# Tx_power.net
KiCad netlist of a schematic drawn in Altium Designer
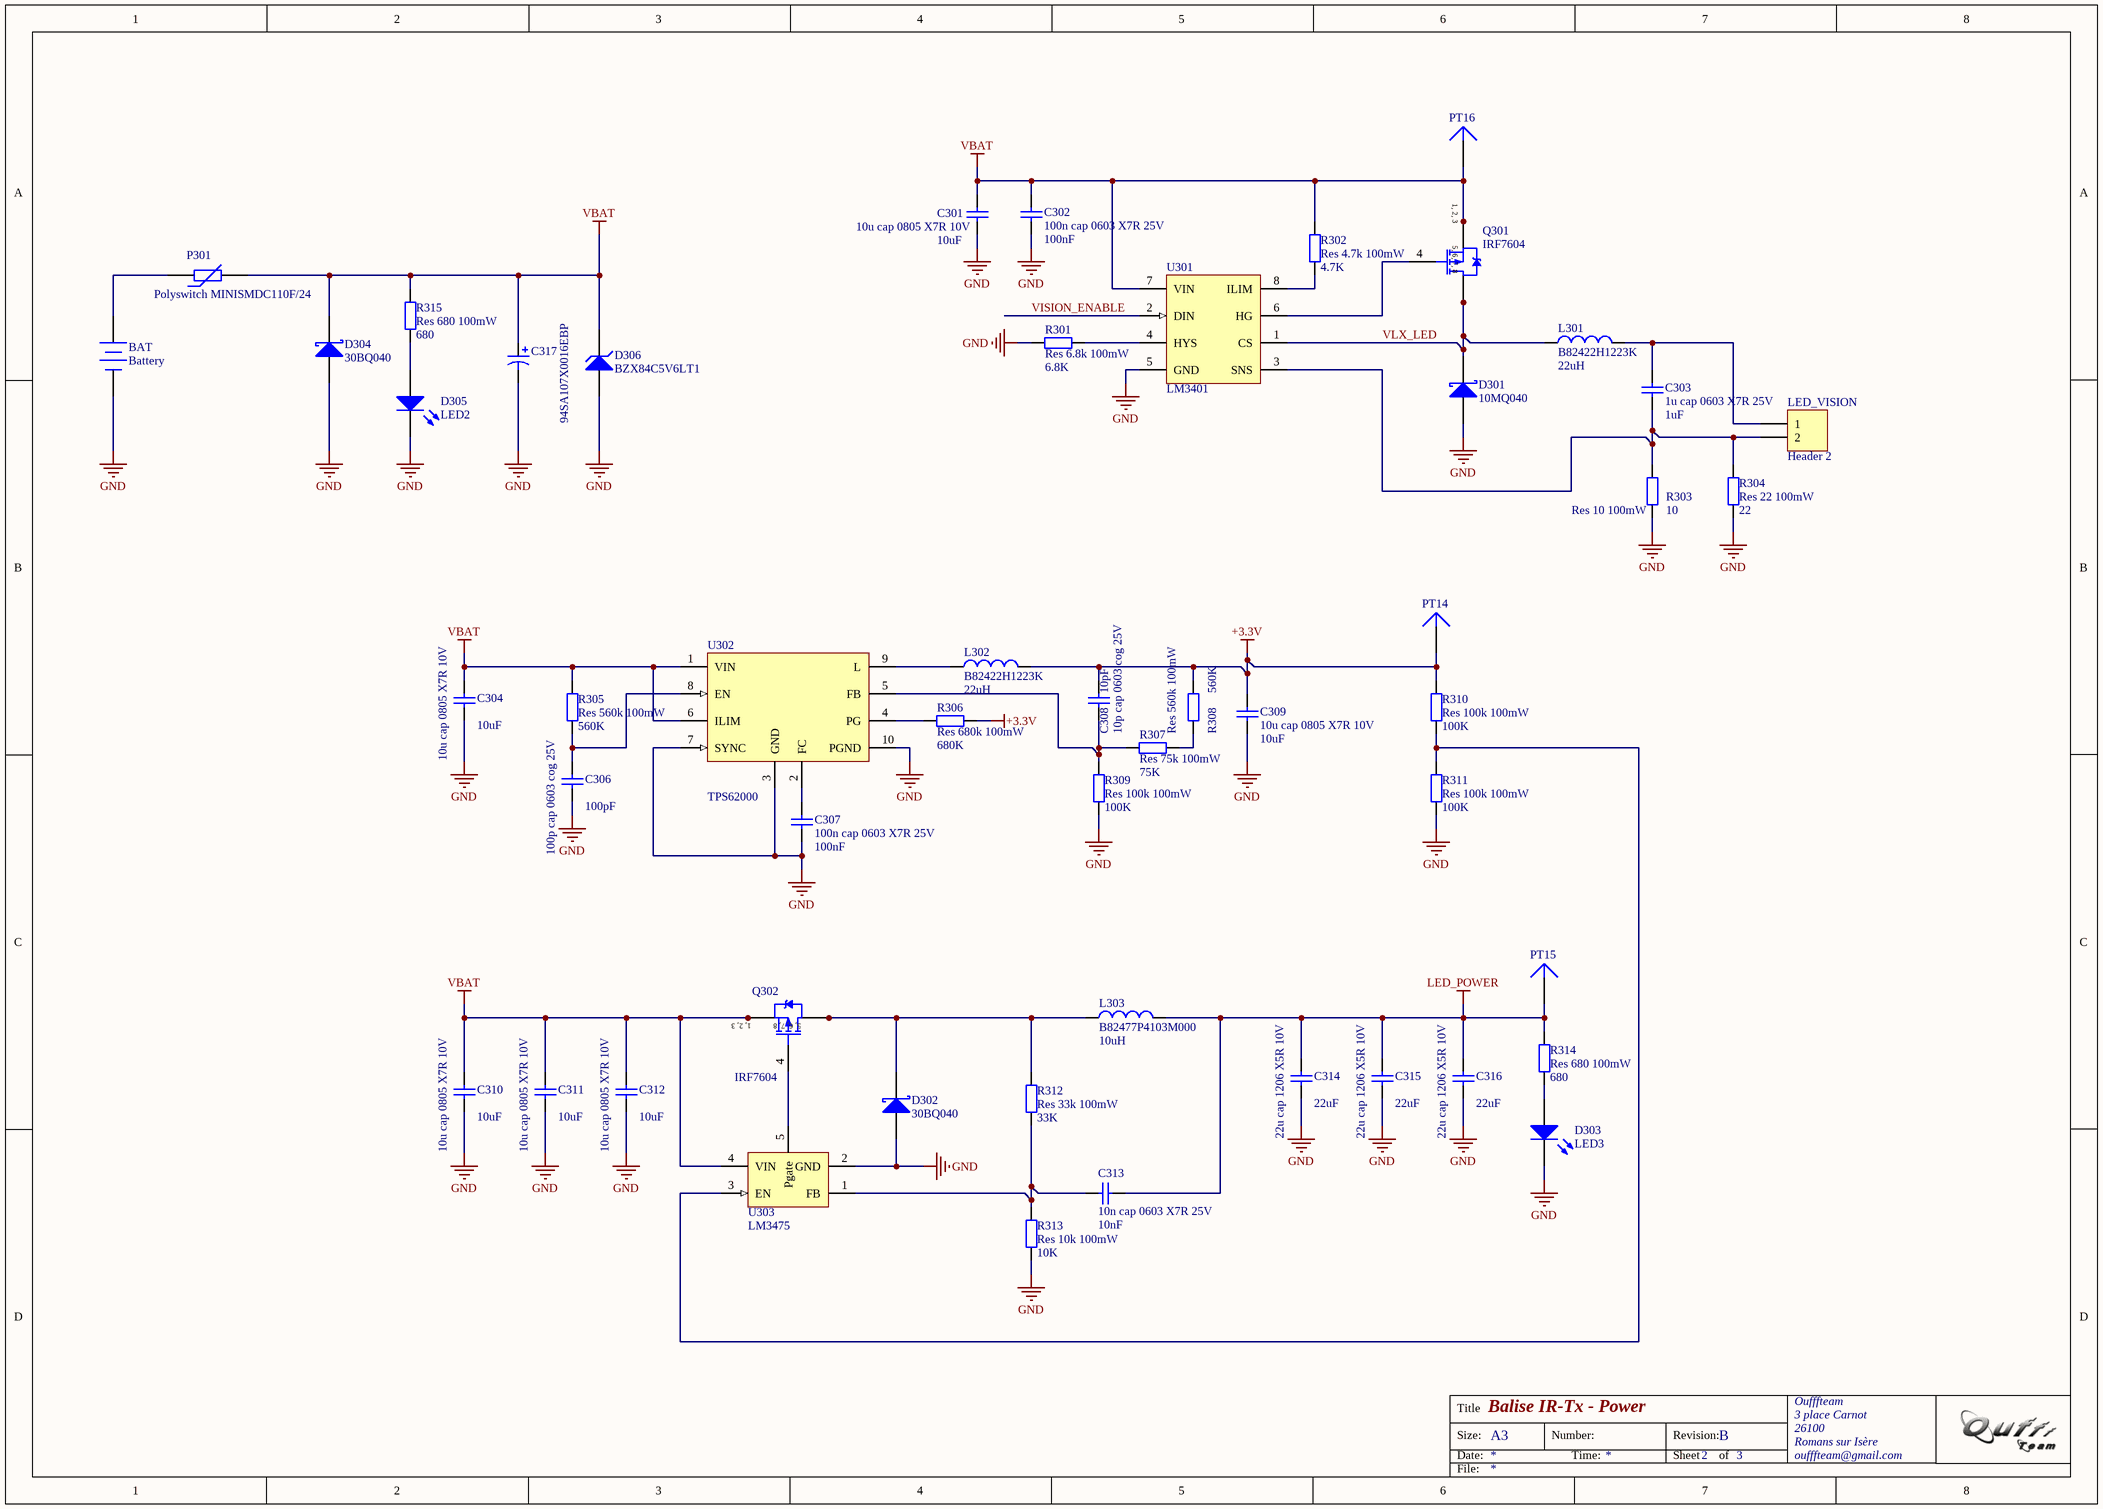
[diagram p0: Tx_power.SchDoc]

(export (version "E")
  (design (tool "Eeschema 10.0.6"))
  (components
    (comp (ref "BAT")
      (value "Battery")
      (footprint "BAT-2")
      (description "Multicell Battery")
      (fields (field (name "PUBLISHER") "Altium Limited"))
      (libsource (lib "Miscellaneous Devices") (part "Battery"))
    )
    (comp (ref "C301")
      (value "10u cap 0805 X7R 10V")
      (footprint "0805")
      (description "Capacitor")
      (fields (field (name "ALTIUM_VALUE") "10uF") (field (name "PUBLISHER") "Altium Limited"))
      (libsource (lib "Miscellaneous Devices") (part "Cap"))
    )
    (comp (ref "C302")
      (value "100n cap 0603 X7R 25V")
      (footprint "0603")
      (description "Capacitor")
      (fields (field (name "ALTIUM_VALUE") "100nF") (field (name "PUBLISHER") "Altium Limited"))
      (libsource (lib "Miscellaneous Devices") (part "Cap"))
    )
    (comp (ref "C303")
      (value "1u cap 0603 X7R 25V")
      (footprint "0603")
      (description "Capacitor")
      (fields (field (name "ALTIUM_VALUE") "1uF") (field (name "PUBLISHER") "Altium Limited"))
      (libsource (lib "Miscellaneous Devices") (part "Cap"))
    )
    (comp (ref "C304")
      (value "10u cap 0805 X7R 10V")
      (footprint "0805")
      (description "Capacitor")
      (fields (field (name "ALTIUM_VALUE") "10uF") (field (name "PUBLISHER") "Altium Limited"))
      (libsource (lib "Miscellaneous Devices") (part "Cap"))
    )
    (comp (ref "C306")
      (value "100p cap 0603 cog 25V")
      (footprint "0603")
      (description "Capacitor")
      (fields (field (name "ALTIUM_VALUE") "100pF") (field (name "PUBLISHER") "Altium Limited"))
      (libsource (lib "Miscellaneous Devices") (part "Cap"))
    )
    (comp (ref "C307")
      (value "100n cap 0603 X7R 25V")
      (footprint "0603")
      (description "Capacitor")
      (fields (field (name "ALTIUM_VALUE") "100nF") (field (name "PUBLISHER") "Altium Limited"))
      (libsource (lib "Miscellaneous Devices") (part "Cap"))
    )
    (comp (ref "C308")
      (value "10p cap 0603 cog 25V")
      (footprint "0603")
      (description "Capacitor")
      (fields (field (name "ALTIUM_VALUE") "10pF") (field (name "PUBLISHER") "Altium Limited"))
      (libsource (lib "Miscellaneous Devices") (part "Cap"))
    )
    (comp (ref "C309")
      (value "10u cap 0805 X7R 10V")
      (footprint "0805")
      (description "Capacitor")
      (fields (field (name "ALTIUM_VALUE") "10uF") (field (name "PUBLISHER") "Altium Limited"))
      (libsource (lib "Miscellaneous Devices") (part "Cap"))
    )
    (comp (ref "C310")
      (value "10u cap 0805 X7R 10V")
      (footprint "0805")
      (description "Capacitor")
      (fields (field (name "ALTIUM_VALUE") "10uF") (field (name "PUBLISHER") "Altium Limited"))
      (libsource (lib "Miscellaneous Devices") (part "Cap"))
    )
    (comp (ref "C311")
      (value "10u cap 0805 X7R 10V")
      (footprint "0805")
      (description "Capacitor")
      (fields (field (name "ALTIUM_VALUE") "10uF") (field (name "PUBLISHER") "Altium Limited"))
      (libsource (lib "Miscellaneous Devices") (part "Cap"))
    )
    (comp (ref "C312")
      (value "10u cap 0805 X7R 10V")
      (footprint "0805")
      (description "Capacitor")
      (fields (field (name "ALTIUM_VALUE") "10uF") (field (name "PUBLISHER") "Altium Limited"))
      (libsource (lib "Miscellaneous Devices") (part "Cap"))
    )
    (comp (ref "C313")
      (value "10n cap 0603 X7R 25V")
      (footprint "0603")
      (description "Capacitor")
      (fields (field (name "ALTIUM_VALUE") "10nF") (field (name "PUBLISHER") "Altium Limited"))
      (libsource (lib "Miscellaneous Devices") (part "Cap"))
    )
    (comp (ref "C314")
      (value "22u cap 1206 X5R 10V")
      (footprint "1206")
      (description "Capacitor")
      (fields (field (name "ALTIUM_VALUE") "22uF") (field (name "PUBLISHER") "Altium Limited"))
      (libsource (lib "Miscellaneous Devices") (part "Cap"))
    )
    (comp (ref "C315")
      (value "22u cap 1206 X5R 10V")
      (footprint "1206")
      (description "Capacitor")
      (fields (field (name "ALTIUM_VALUE") "22uF") (field (name "PUBLISHER") "Altium Limited"))
      (libsource (lib "Miscellaneous Devices") (part "Cap"))
    )
    (comp (ref "C316")
      (value "22u cap 1206 X5R 10V")
      (footprint "1206")
      (description "Capacitor")
      (fields (field (name "ALTIUM_VALUE") "22uF") (field (name "PUBLISHER") "Altium Limited"))
      (libsource (lib "Miscellaneous Devices") (part "Cap"))
    )
    (comp (ref "C317")
      (value "94SA107X0016EBP")
      (footprint "E")
      (description "Solid Aluminum Capacitor with Organic Semiconductor Electrolyte: 100uF, 16V, Bulk Pack")
      (fields (field (name "PUBLISHER") "Altium Limited"))
      (libsource (lib "Vishay Electrolytic Radial-Lead Capacitor") (part "94SA107X0016EBP"))
    )
    (comp (ref "D301")
      (value "10MQ040")
      (footprint "D-64")
      (description "Schottky Rectifier")
      (fields (field (name "PUBLISHER") "Altium Limited"))
      (libsource (lib "IR Rectifier - Schottky") (part "10MQ040"))
    )
    (comp (ref "D302")
      (value "30BQ040")
      (footprint "SMC")
      (description "Schottky Rectifier")
      (fields (field (name "PUBLISHER") "Altium Limited"))
      (libsource (lib "IR Rectifier - Schottky") (part "30BQ040"))
    )
    (comp (ref "D303")
      (value "LED3")
      (footprint "0603")
      (description "Typical BLUE SiC LED")
      (fields (field (name "PUBLISHER") "Altium Limited"))
      (libsource (lib "Miscellaneous Devices") (part "LED3"))
    )
    (comp (ref "D304")
      (value "30BQ040")
      (footprint "SMC")
      (description "Schottky Rectifier")
      (fields (field (name "PUBLISHER") "Altium Limited"))
      (libsource (lib "IR Rectifier - Schottky") (part "30BQ040"))
    )
    (comp (ref "D305")
      (value "LED2")
      (footprint "0603")
      (description "Typical RED, GREEN, YELLOW, AMBER GaAs LED")
      (fields (field (name "PUBLISHER") "Altium Limited"))
      (libsource (lib "Miscellaneous Devices") (part "LED2"))
    )
    (comp (ref "D306")
      (value "BZX84C5V6LT1")
      (footprint "318-07")
      (description "Zener Voltage Regulator Diode")
      (fields (field (name "PUBLISHER") "Altium Limited"))
      (libsource (lib "Motorola Discrete Diode") (part "BZX84C5V6LT1"))
    )
    (comp (ref "L301")
      (value "B82422H1223K")
      (footprint "1210")
      (description "Inductor")
      (fields (field (name "ALTIUM_VALUE") "22uH") (field (name "PUBLISHER") "Altium Limited"))
      (libsource (lib "Miscellaneous Devices") (part "Inductor"))
    )
    (comp (ref "L302")
      (value "B82422H1223K")
      (footprint "1210")
      (description "Inductor")
      (fields (field (name "ALTIUM_VALUE") "22uH") (field (name "PUBLISHER") "Altium Limited"))
      (libsource (lib "Miscellaneous Devices") (part "Inductor"))
    )
    (comp (ref "L303")
      (value "B82477P4103M000")
      (footprint "B82477P4103M000")
      (description "Inductor")
      (fields (field (name "ALTIUM_VALUE") "10uH") (field (name "PUBLISHER") "Altium Limited"))
      (libsource (lib "Miscellaneous Devices") (part "Inductor"))
    )
    (comp (ref "LED_VISION")
      (value "Header 2")
      (footprint "HDR1X2")
      (description "Header, 2-Pin")
      (fields (field (name "PUBLISHER") "Altium Limited"))
      (libsource (lib "Miscellaneous Connectors") (part "Header 2"))
    )
    (comp (ref "P301")
      (value "Polyswitch MINISMDC110F/24")
      (footprint "1812")
      (description "Varistor (Voltage-Sensitive Resistor)")
      (fields (field (name "PUBLISHER") "Altium Limited"))
      (libsource (lib "Miscellaneous Devices") (part "Res Varistor"))
    )
    (comp (ref "PT14")
      (value "Plug")
      (footprint "TP")
      (fields (field (name "PUBLISHER") "Altium Limited"))
      (libsource (lib "Miscellaneous Connectors") (part "Plug"))
    )
    (comp (ref "PT15")
      (value "Plug")
      (footprint "TP")
      (fields (field (name "PUBLISHER") "Altium Limited"))
      (libsource (lib "Miscellaneous Connectors") (part "Plug"))
    )
    (comp (ref "PT16")
      (value "Plug")
      (footprint "TP")
      (fields (field (name "PUBLISHER") "Altium Limited"))
      (libsource (lib "Miscellaneous Connectors") (part "Plug"))
    )
    (comp (ref "Q301")
      (value "IRF7604")
      (footprint "Micro8")
      (description "HEXFET Power MOSFET")
      (fields (field (name "PUBLISHER") "Altium Limited"))
      (libsource (lib "IR Discrete MOSFET - Power") (part "IRF7604"))
    )
    (comp (ref "Q302")
      (value "IRF7604")
      (footprint "Micro8")
      (description "HEXFET Power MOSFET")
      (fields (field (name "PUBLISHER") "Altium Limited"))
      (libsource (lib "IR Discrete MOSFET - Power") (part "IRF7604"))
    )
    (comp (ref "R301")
      (value "Res 6.8k 100mW")
      (footprint "0603")
      (description "Resistor")
      (fields (field (name "ALTIUM_VALUE") "6.8K") (field (name "PUBLISHER") "Altium Limited"))
      (libsource (lib "") (part "Res2_1"))
    )
    (comp (ref "R302")
      (value "Res 4.7k 100mW")
      (footprint "0603")
      (description "Resistor")
      (fields (field (name "ALTIUM_VALUE") "4.7K") (field (name "PUBLISHER") "Altium Limited"))
      (libsource (lib "Miscellaneous Devices") (part "Res2"))
    )
    (comp (ref "R303")
      (value "Res 10 100mW")
      (footprint "0603")
      (description "Resistor")
      (fields (field (name "ALTIUM_VALUE") "10") (field (name "PUBLISHER") "Altium Limited"))
      (libsource (lib "Miscellaneous Devices") (part "Res2"))
    )
    (comp (ref "R304")
      (value "Res 22 100mW")
      (footprint "0603")
      (description "Resistor")
      (fields (field (name "ALTIUM_VALUE") "22") (field (name "PUBLISHER") "Altium Limited"))
      (libsource (lib "Miscellaneous Devices") (part "Res2"))
    )
    (comp (ref "R305")
      (value "Res 560k 100mW")
      (footprint "0603")
      (description "Resistor")
      (fields (field (name "ALTIUM_VALUE") "560K") (field (name "PUBLISHER") "Altium Limited"))
      (libsource (lib "Miscellaneous Devices") (part "Res2"))
    )
    (comp (ref "R306")
      (value "Res 680k 100mW")
      (footprint "0603")
      (description "Resistor")
      (fields (field (name "ALTIUM_VALUE") "680K") (field (name "PUBLISHER") "Altium Limited"))
      (libsource (lib "") (part "Res2_1"))
    )
    (comp (ref "R307")
      (value "Res 75k 100mW")
      (footprint "0603")
      (description "Resistor")
      (fields (field (name "ALTIUM_VALUE") "75K") (field (name "PUBLISHER") "Altium Limited"))
      (libsource (lib "") (part "Res2_1"))
    )
    (comp (ref "R308")
      (value "Res 560k 100mW")
      (footprint "0603")
      (description "Resistor")
      (fields (field (name "ALTIUM_VALUE") "560K") (field (name "PUBLISHER") "Altium Limited"))
      (libsource (lib "Miscellaneous Devices") (part "Res2"))
    )
    (comp (ref "R309")
      (value "Res 100k 100mW")
      (footprint "0603")
      (description "Resistor")
      (fields (field (name "ALTIUM_VALUE") "100K") (field (name "PUBLISHER") "Altium Limited"))
      (libsource (lib "Miscellaneous Devices") (part "Res2"))
    )
    (comp (ref "R310")
      (value "Res 100k 100mW")
      (footprint "0603")
      (description "Resistor")
      (fields (field (name "ALTIUM_VALUE") "100K") (field (name "PUBLISHER") "Altium Limited"))
      (libsource (lib "Miscellaneous Devices") (part "Res2"))
    )
    (comp (ref "R311")
      (value "Res 100k 100mW")
      (footprint "0603")
      (description "Resistor")
      (fields (field (name "ALTIUM_VALUE") "100K") (field (name "PUBLISHER") "Altium Limited"))
      (libsource (lib "Miscellaneous Devices") (part "Res2"))
    )
    (comp (ref "R312")
      (value "Res 33k 100mW")
      (footprint "0603")
      (description "Resistor")
      (fields (field (name "ALTIUM_VALUE") "33K") (field (name "PUBLISHER") "Altium Limited"))
      (libsource (lib "Miscellaneous Devices") (part "Res2"))
    )
    (comp (ref "R313")
      (value "Res 10k 100mW")
      (footprint "0603")
      (description "Resistor")
      (fields (field (name "ALTIUM_VALUE") "10K") (field (name "PUBLISHER") "Altium Limited"))
      (libsource (lib "Miscellaneous Devices") (part "Res2"))
    )
    (comp (ref "R314")
      (value "Res 680 100mW")
      (footprint "0603")
      (description "Resistor")
      (fields (field (name "ALTIUM_VALUE") "680") (field (name "PUBLISHER") "Altium Limited"))
      (libsource (lib "Miscellaneous Devices") (part "Res2"))
    )
    (comp (ref "R315")
      (value "Res 680 100mW")
      (footprint "0603")
      (description "Resistor")
      (fields (field (name "ALTIUM_VALUE") "680") (field (name "PUBLISHER") "Altium Limited"))
      (libsource (lib "Miscellaneous Devices") (part "Res2"))
    )
    (comp (ref "U301")
      (value "LM3401")
      (footprint "MSOP8")
      (description "Hysteretic PFET Controller for High Power LED Drive")
      (libsource (lib "Oufff_Lib2") (part "LM3401"))
    )
    (comp (ref "U302")
      (value "TPS62000")
      (footprint "MS10")
      (description "HIGH-EFFICIENCY STEP-DOWN LOW POWER DC-DC CONVERTER")
      (libsource (lib "Oufff_Lib2") (part "TPS6200x"))
    )
    (comp (ref "U303")
      (value "LM3475")
      (footprint "SOT23-5")
      (description "Hysteretic PFET Buck Controller")
      (libsource (lib "Oufff_Lib2") (part "LM3475"))
    )
  )
  (nets
    (net (code "1") (name "+3.3V") (class "Default")
      (node (ref "C308") (pin "2") (pinfunction "2_2") (pintype "passive"))
      (node (ref "C309") (pin "2") (pinfunction "2_2") (pintype "passive"))
      (node (ref "L302") (pin "2") (pinfunction "2_2") (pintype "passive"))
      (node (ref "PT14") (pin "1") (pinfunction "1_1") (pintype "passive"))
      (node (ref "R306") (pin "2") (pinfunction "2_2") (pintype "passive"))
      (node (ref "R308") (pin "2") (pinfunction "2_2") (pintype "passive"))
      (node (ref "R310") (pin "2") (pinfunction "2_2") (pintype "passive"))
    )
    (net (code "2") (name "/VISION_ENABLE") (class "Default")
      (node (ref "U301") (pin "2") (pinfunction "DIN_2") (pintype "input"))
    )
    (net (code "3") (name "/VLX_LED") (class "Default")
      (node (ref "D301") (pin "2") (pinfunction "K_2") (pintype "passive"))
      (node (ref "L301") (pin "1") (pinfunction "1_1") (pintype "passive"))
      (node (ref "Q301") (pin "5") (pinfunction "D_5") (pintype "passive"))
      (node (ref "Q301") (pin "6") (pinfunction "D_6") (pintype "passive"))
      (node (ref "Q301") (pin "7") (pinfunction "D_7") (pintype "passive"))
      (node (ref "Q301") (pin "8") (pinfunction "D_8") (pintype "passive"))
      (node (ref "U301") (pin "1") (pinfunction "CS_1") (pintype "passive"))
    )
    (net (code "4") (name "GND") (class "Default")
      (node (ref "BAT") (pin "2") (pinfunction "-_2") (pintype "passive"))
      (node (ref "C301") (pin "1") (pinfunction "1_1") (pintype "passive"))
      (node (ref "C302") (pin "1") (pinfunction "1_1") (pintype "passive"))
      (node (ref "C304") (pin "1") (pinfunction "1_1") (pintype "passive"))
      (node (ref "C306") (pin "1") (pinfunction "1_1") (pintype "passive"))
      (node (ref "C307") (pin "1") (pinfunction "1_1") (pintype "passive"))
      (node (ref "C309") (pin "1") (pinfunction "1_1") (pintype "passive"))
      (node (ref "C310") (pin "1") (pinfunction "1_1") (pintype "passive"))
      (node (ref "C311") (pin "1") (pinfunction "1_1") (pintype "passive"))
      (node (ref "C312") (pin "1") (pinfunction "1_1") (pintype "passive"))
      (node (ref "C314") (pin "1") (pinfunction "1_1") (pintype "passive"))
      (node (ref "C315") (pin "1") (pinfunction "1_1") (pintype "passive"))
      (node (ref "C316") (pin "1") (pinfunction "1_1") (pintype "passive"))
      (node (ref "C317") (pin "2") (pinfunction "2_2") (pintype "passive"))
      (node (ref "D301") (pin "1") (pinfunction "A_1") (pintype "passive"))
      (node (ref "D302") (pin "1") (pinfunction "A_1") (pintype "passive"))
      (node (ref "D303") (pin "2") (pinfunction "K_2") (pintype "passive"))
      (node (ref "D304") (pin "1") (pinfunction "A_1") (pintype "passive"))
      (node (ref "D305") (pin "2") (pinfunction "K_2") (pintype "passive"))
      (node (ref "D306") (pin "1") (pinfunction "A_1") (pintype "passive"))
      (node (ref "R301") (pin "1") (pinfunction "1_1") (pintype "passive"))
      (node (ref "R303") (pin "1") (pinfunction "1_1") (pintype "passive"))
      (node (ref "R304") (pin "1") (pinfunction "1_1") (pintype "passive"))
      (node (ref "R309") (pin "1") (pinfunction "1_1") (pintype "passive"))
      (node (ref "R311") (pin "1") (pinfunction "1_1") (pintype "passive"))
      (node (ref "R313") (pin "1") (pinfunction "1_1") (pintype "passive"))
      (node (ref "U301") (pin "5") (pinfunction "GND_5") (pintype "power_in"))
      (node (ref "U302") (pin "10") (pinfunction "PGND_10") (pintype "power_in"))
      (node (ref "U302") (pin "3") (pinfunction "GND_3") (pintype "power_in"))
      (node (ref "U302") (pin "7") (pinfunction "SYNC_7") (pintype "input"))
      (node (ref "U303") (pin "2") (pinfunction "GND_2") (pintype "power_in"))
    )
    (net (code "5") (name "LED_POWER") (class "Default")
      (node (ref "C313") (pin "2") (pinfunction "2_2") (pintype "passive"))
      (node (ref "C314") (pin "2") (pinfunction "2_2") (pintype "passive"))
      (node (ref "C315") (pin "2") (pinfunction "2_2") (pintype "passive"))
      (node (ref "C316") (pin "2") (pinfunction "2_2") (pintype "passive"))
      (node (ref "L303") (pin "2") (pinfunction "2_2") (pintype "passive"))
      (node (ref "PT15") (pin "1") (pinfunction "1_1") (pintype "passive"))
      (node (ref "R314") (pin "2") (pinfunction "2_2") (pintype "passive"))
    )
    (net (code "6") (name "Net-(BAT-+)") (class "Default")
      (node (ref "BAT") (pin "1") (pinfunction "+_1") (pintype "passive"))
      (node (ref "P301") (pin "1") (pinfunction "1_1") (pintype "passive"))
    )
    (net (code "7") (name "Net-(C303-Pad2)") (class "Default")
      (node (ref "C303") (pin "2") (pinfunction "2_2") (pintype "passive"))
      (node (ref "L301") (pin "2") (pinfunction "2_2") (pintype "passive"))
      (node (ref "LED_VISION") (pin "1") (pinfunction "1_1") (pintype "passive"))
    )
    (net (code "8") (name "Net-(D302-K)") (class "Default")
      (node (ref "D302") (pin "2") (pinfunction "K_2") (pintype "passive"))
      (node (ref "L303") (pin "1") (pinfunction "1_1") (pintype "passive"))
      (node (ref "Q302") (pin "5") (pinfunction "D_5") (pintype "passive"))
      (node (ref "Q302") (pin "6") (pinfunction "D_6") (pintype "passive"))
      (node (ref "Q302") (pin "7") (pinfunction "D_7") (pintype "passive"))
      (node (ref "Q302") (pin "8") (pinfunction "D_8") (pintype "passive"))
      (node (ref "R312") (pin "2") (pinfunction "2_2") (pintype "passive"))
    )
    (net (code "9") (name "Net-(D303-A)") (class "Default")
      (node (ref "D303") (pin "1") (pinfunction "A_1") (pintype "passive"))
      (node (ref "R314") (pin "1") (pinfunction "1_1") (pintype "passive"))
    )
    (net (code "10") (name "Net-(D305-A)") (class "Default")
      (node (ref "D305") (pin "1") (pinfunction "A_1") (pintype "passive"))
      (node (ref "R315") (pin "1") (pinfunction "1_1") (pintype "passive"))
    )
    (net (code "11") (name "Net-(Q301-G)") (class "Default")
      (node (ref "Q301") (pin "4") (pinfunction "G_4") (pintype "passive"))
      (node (ref "U301") (pin "6") (pinfunction "HG_6") (pintype "passive"))
    )
    (net (code "12") (name "Net-(Q302-G)") (class "Default")
      (node (ref "Q302") (pin "4") (pinfunction "G_4") (pintype "passive"))
      (node (ref "U303") (pin "5") (pinfunction "Pgate_5") (pintype "power_in"))
    )
    (net (code "13") (name "Net-(R307-Pad2)") (class "Default")
      (node (ref "R307") (pin "2") (pinfunction "2_2") (pintype "passive"))
      (node (ref "R308") (pin "1") (pinfunction "1_1") (pintype "passive"))
    )
    (net (code "14") (name "Net-(U301-HYS)") (class "Default")
      (node (ref "R301") (pin "2") (pinfunction "2_2") (pintype "passive"))
      (node (ref "U301") (pin "4") (pinfunction "HYS_4") (pintype "passive"))
    )
    (net (code "15") (name "Net-(U301-ILIM)") (class "Default")
      (node (ref "R302") (pin "1") (pinfunction "1_1") (pintype "passive"))
      (node (ref "U301") (pin "8") (pinfunction "ILIM_8") (pintype "passive"))
    )
    (net (code "16") (name "Net-(U301-SNS)") (class "Default")
      (node (ref "C303") (pin "1") (pinfunction "1_1") (pintype "passive"))
      (node (ref "LED_VISION") (pin "2") (pinfunction "2_2") (pintype "passive"))
      (node (ref "R303") (pin "2") (pinfunction "2_2") (pintype "passive"))
      (node (ref "R304") (pin "2") (pinfunction "2_2") (pintype "passive"))
      (node (ref "U301") (pin "3") (pinfunction "SNS_3") (pintype "passive"))
    )
    (net (code "17") (name "Net-(U302-EN)") (class "Default")
      (node (ref "C306") (pin "2") (pinfunction "2_2") (pintype "passive"))
      (node (ref "R305") (pin "1") (pinfunction "1_1") (pintype "passive"))
      (node (ref "U302") (pin "8") (pinfunction "EN_8") (pintype "input"))
    )
    (net (code "18") (name "Net-(U302-FB)") (class "Default")
      (node (ref "C308") (pin "1") (pinfunction "1_1") (pintype "passive"))
      (node (ref "R307") (pin "1") (pinfunction "1_1") (pintype "passive"))
      (node (ref "R309") (pin "2") (pinfunction "2_2") (pintype "passive"))
      (node (ref "U302") (pin "5") (pinfunction "FB_5") (pintype "passive"))
    )
    (net (code "19") (name "Net-(U302-FC)") (class "Default")
      (node (ref "C307") (pin "2") (pinfunction "2_2") (pintype "passive"))
      (node (ref "U302") (pin "2") (pinfunction "FC_2") (pintype "passive"))
    )
    (net (code "20") (name "Net-(U302-L)") (class "Default")
      (node (ref "L302") (pin "1") (pinfunction "1_1") (pintype "passive"))
      (node (ref "U302") (pin "9") (pinfunction "L_9") (pintype "power_in"))
    )
    (net (code "21") (name "Net-(U302-PG)") (class "Default")
      (node (ref "R306") (pin "1") (pinfunction "1_1") (pintype "passive"))
      (node (ref "U302") (pin "4") (pinfunction "PG_4") (pintype "open_collector"))
    )
    (net (code "22") (name "Net-(U303-EN)") (class "Default")
      (node (ref "R310") (pin "1") (pinfunction "1_1") (pintype "passive"))
      (node (ref "R311") (pin "2") (pinfunction "2_2") (pintype "passive"))
      (node (ref "U303") (pin "3") (pinfunction "EN_3") (pintype "input"))
    )
    (net (code "23") (name "Net-(U303-FB)") (class "Default")
      (node (ref "C313") (pin "1") (pinfunction "1_1") (pintype "passive"))
      (node (ref "R312") (pin "1") (pinfunction "1_1") (pintype "passive"))
      (node (ref "R313") (pin "2") (pinfunction "2_2") (pintype "passive"))
      (node (ref "U303") (pin "1") (pinfunction "FB_1") (pintype "passive"))
    )
    (net (code "24") (name "VBAT") (class "Default")
      (node (ref "C301") (pin "2") (pinfunction "2_2") (pintype "passive"))
      (node (ref "C302") (pin "2") (pinfunction "2_2") (pintype "passive"))
      (node (ref "C304") (pin "2") (pinfunction "2_2") (pintype "passive"))
      (node (ref "C310") (pin "2") (pinfunction "2_2") (pintype "passive"))
      (node (ref "C311") (pin "2") (pinfunction "2_2") (pintype "passive"))
      (node (ref "C312") (pin "2") (pinfunction "2_2") (pintype "passive"))
      (node (ref "C317") (pin "1") (pinfunction "1_1") (pintype "passive"))
      (node (ref "D304") (pin "2") (pinfunction "K_2") (pintype "passive"))
      (node (ref "D306") (pin "3") (pinfunction "K_3") (pintype "passive"))
      (node (ref "P301") (pin "2") (pinfunction "2_2") (pintype "passive"))
      (node (ref "PT16") (pin "1") (pinfunction "1_1") (pintype "passive"))
      (node (ref "Q301") (pin "1") (pinfunction "S_1") (pintype "passive"))
      (node (ref "Q301") (pin "2") (pinfunction "S_2") (pintype "passive"))
      (node (ref "Q301") (pin "3") (pinfunction "S_3") (pintype "passive"))
      (node (ref "Q302") (pin "1") (pinfunction "S_1") (pintype "passive"))
      (node (ref "Q302") (pin "2") (pinfunction "S_2") (pintype "passive"))
      (node (ref "Q302") (pin "3") (pinfunction "S_3") (pintype "passive"))
      (node (ref "R302") (pin "2") (pinfunction "2_2") (pintype "passive"))
      (node (ref "R305") (pin "2") (pinfunction "2_2") (pintype "passive"))
      (node (ref "R315") (pin "2") (pinfunction "2_2") (pintype "passive"))
      (node (ref "U301") (pin "7") (pinfunction "VIN_7") (pintype "power_in"))
      (node (ref "U302") (pin "1") (pinfunction "VIN_1") (pintype "power_in"))
      (node (ref "U302") (pin "6") (pinfunction "ILIM_6") (pintype "passive"))
      (node (ref "U303") (pin "4") (pinfunction "VIN_4") (pintype "power_in"))
    )
  )
)
